# Flash_eMMC_MicroSD.net
KiCad netlist of a schematic drawn in Altium Designer
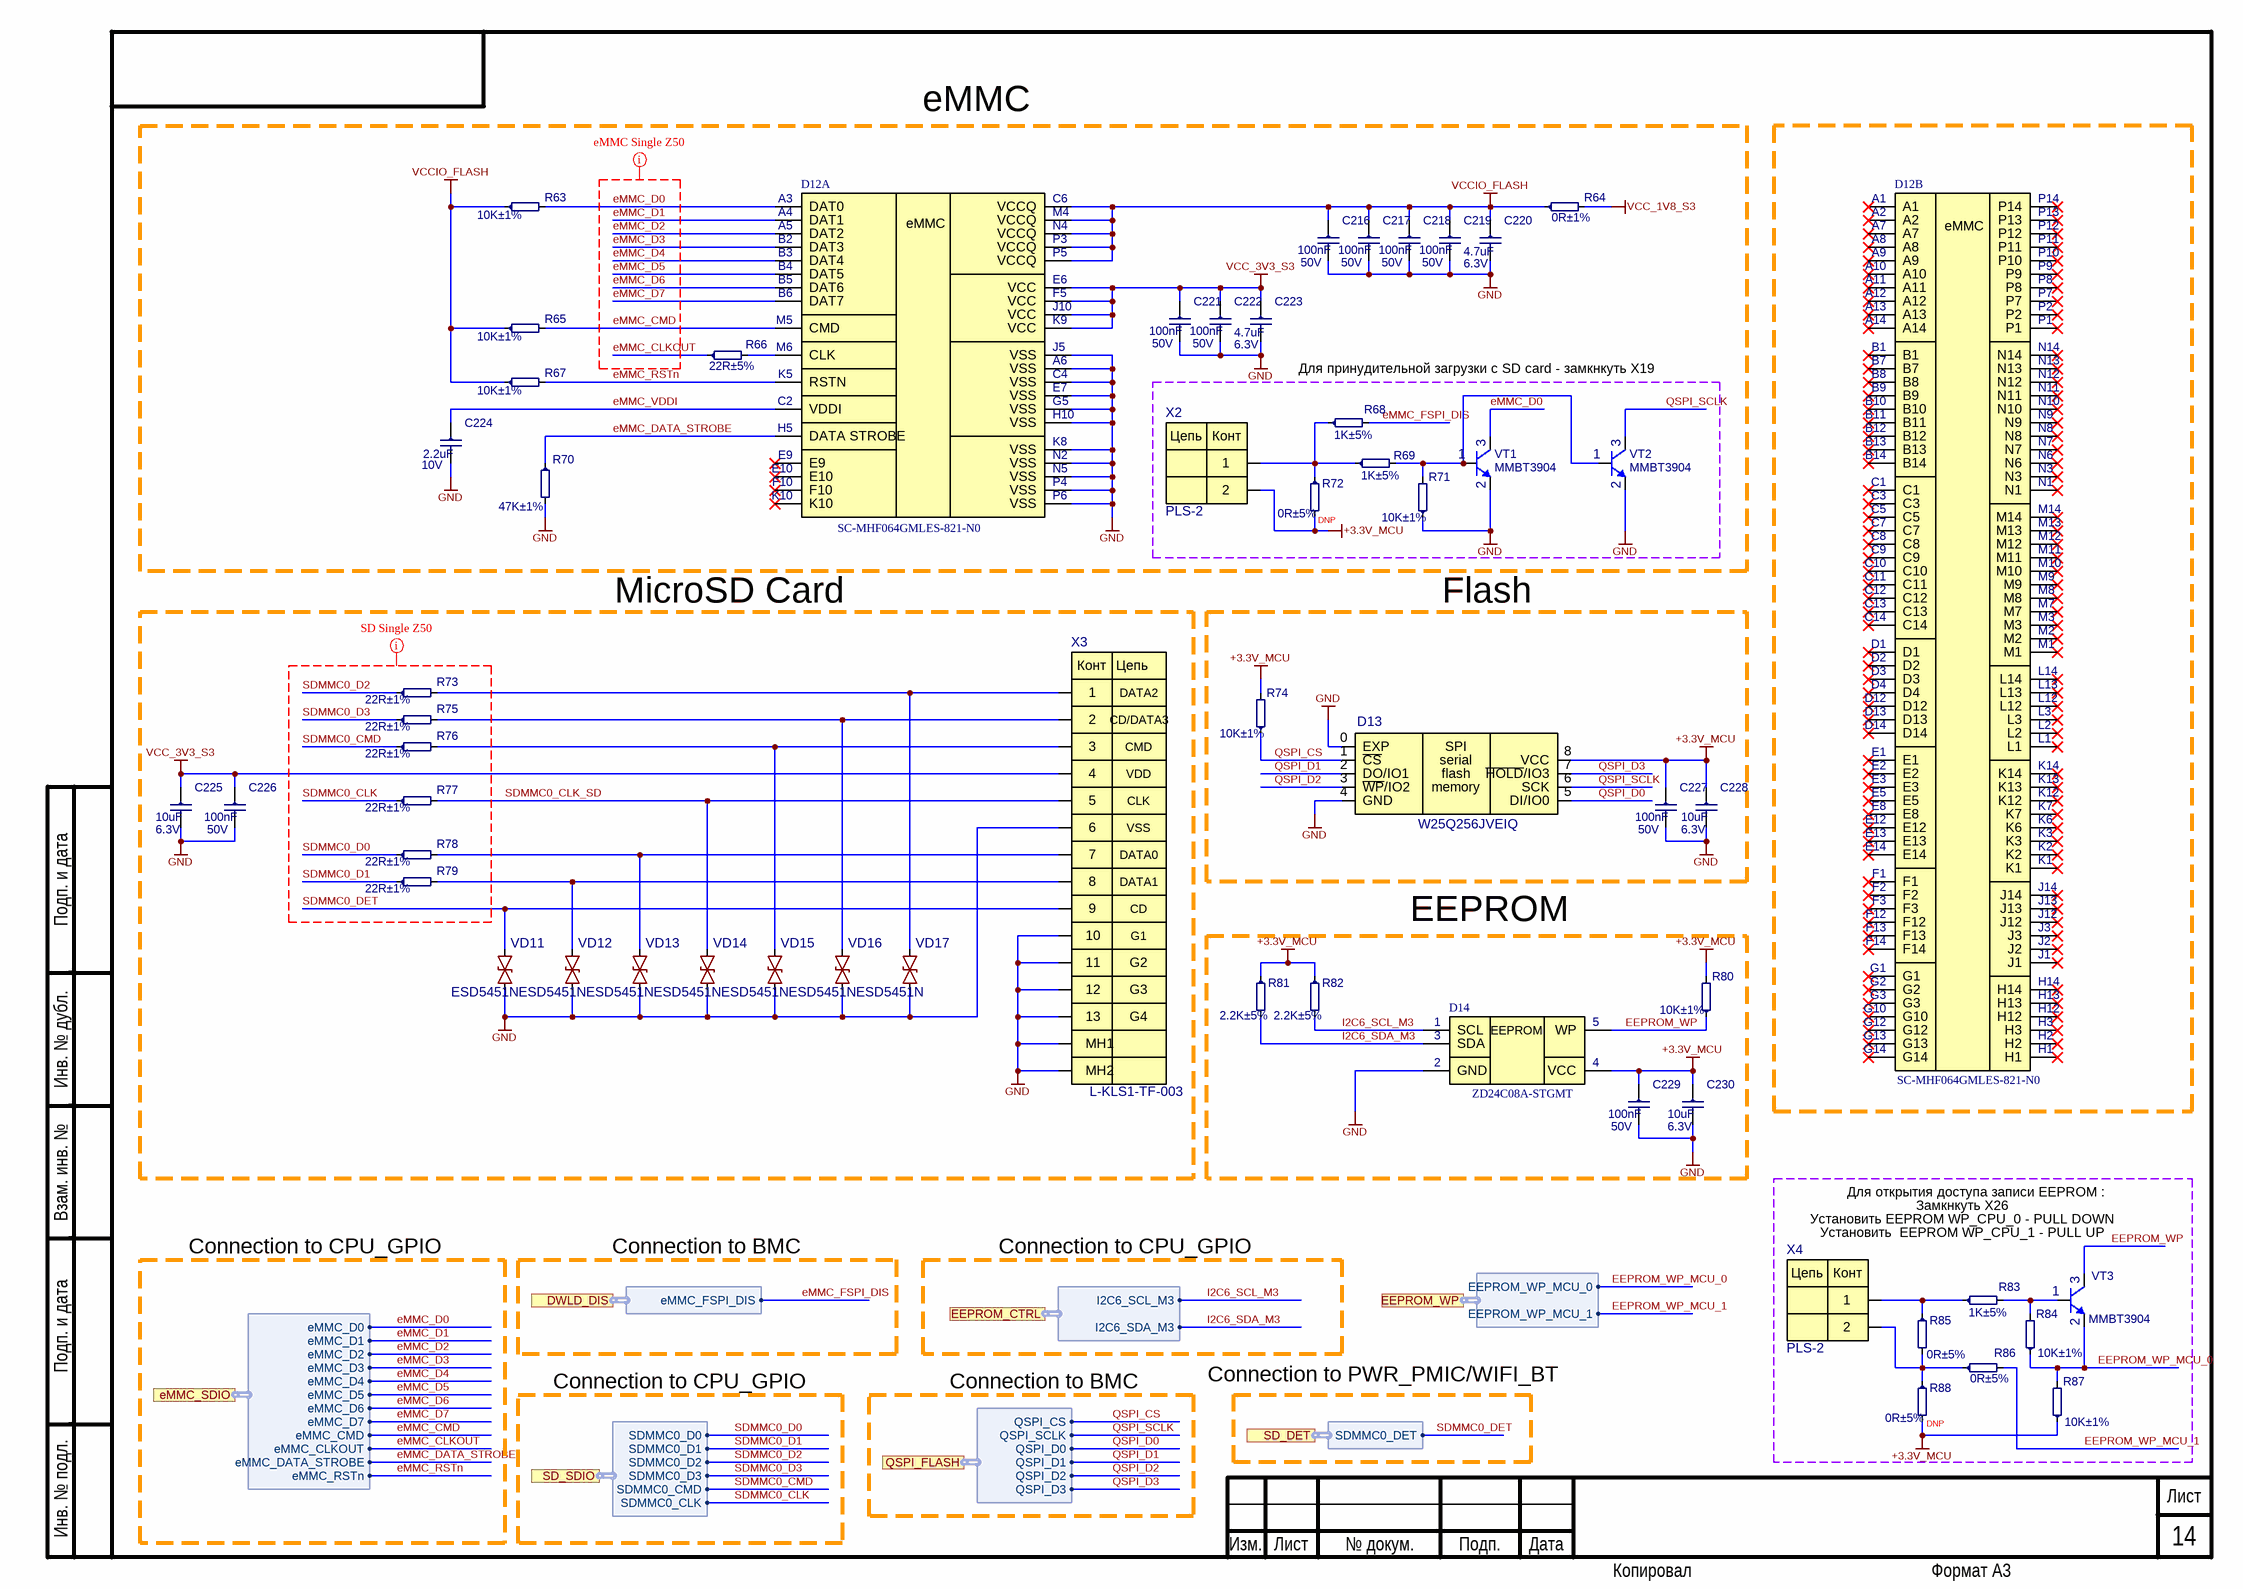
[diagram p0: Flash_eMMC_MicroSD.SchDoc]

(export (version "E")
  (design (tool "Eeschema 10.0.6"))
  (components
    (comp (ref "C216")
      (value "100nF")
      (footprint "C0402")
      (description "Ceramic Capacitor 0402 100nF ±10% 50V X7R")
      (fields
        (field (name "VOLTAGE") "50V")
        (field (name "PART NUMBER") "0402-X7R-50V-0.1uF±10%")
        (field (name "TOLERANCE") "10%")
      )
      (libsource (lib "ATB") (part "C"))
    )
    (comp (ref "C217")
      (value "100nF")
      (footprint "C0402")
      (description "Ceramic Capacitor 0402 100nF ±10% 50V X7R")
      (fields
        (field (name "VOLTAGE") "50V")
        (field (name "PART NUMBER") "0402-X7R-50V-0.1uF±10%")
        (field (name "TOLERANCE") "10%")
      )
      (libsource (lib "ATB") (part "C"))
    )
    (comp (ref "C218")
      (value "100nF")
      (footprint "C0402")
      (description "Ceramic Capacitor 0402 100nF ±10% 50V X7R")
      (fields
        (field (name "VOLTAGE") "50V")
        (field (name "PART NUMBER") "0402-X7R-50V-0.1uF±10%")
        (field (name "TOLERANCE") "10%")
      )
      (libsource (lib "ATB") (part "C"))
    )
    (comp (ref "C219")
      (value "100nF")
      (footprint "C0402")
      (description "Ceramic Capacitor 0402 100nF ±10% 50V X7R")
      (fields
        (field (name "VOLTAGE") "50V")
        (field (name "PART NUMBER") "0402-X7R-50V-0.1uF±10%")
        (field (name "TOLERANCE") "10%")
      )
      (libsource (lib "ATB") (part "C"))
    )
    (comp (ref "C220")
      (value "4.7uF")
      (footprint "C0402")
      (description "Ceramic Capacitor 0402 4.7uF ±20% 6.3V X5R")
      (fields
        (field (name "VOLTAGE") "6.3V")
        (field (name "PART NUMBER") "0402-X5R-6.3V-4.7uF±20%")
        (field (name "TOLERANCE") "20%")
      )
      (libsource (lib "ATB") (part "C"))
    )
    (comp (ref "C221")
      (value "100nF")
      (footprint "C0402")
      (description "Ceramic Capacitor 0402 100nF ±10% 50V X7R")
      (fields
        (field (name "VOLTAGE") "50V")
        (field (name "PART NUMBER") "0402-X7R-50V-0.1uF±10%")
        (field (name "TOLERANCE") "10%")
      )
      (libsource (lib "ATB") (part "C"))
    )
    (comp (ref "C222")
      (value "100nF")
      (footprint "C0402")
      (description "Ceramic Capacitor 0402 100nF ±10% 50V X7R")
      (fields
        (field (name "VOLTAGE") "50V")
        (field (name "PART NUMBER") "0402-X7R-50V-0.1uF±10%")
        (field (name "TOLERANCE") "10%")
      )
      (libsource (lib "ATB") (part "C"))
    )
    (comp (ref "C223")
      (value "4.7uF")
      (footprint "C0402")
      (description "Ceramic Capacitor 0402 4.7uF ±20% 6.3V X5R")
      (fields
        (field (name "VOLTAGE") "6.3V")
        (field (name "PART NUMBER") "0402-X5R-6.3V-4.7uF±20%")
        (field (name "TOLERANCE") "20%")
      )
      (libsource (lib "ATB") (part "C"))
    )
    (comp (ref "C224")
      (value "2.2uF")
      (footprint "C0402")
      (fields
        (field (name "VOLTAGE") "10V")
        (field (name "PART NUMBER") "0402-X5R-10V-2.2uF±10%")
        (field (name "TOLERANCE") "10%")
        (field (name "MANUFACTURER") "Yageo")
      )
      (libsource (lib "ATB") (part "C"))
    )
    (comp (ref "C225")
      (value "10uF")
      (footprint "C0402")
      (fields
        (field (name "VOLTAGE") "6.3V")
        (field (name "PART NUMBER") "0402-X5R-6.3V-10uF±20%")
        (field (name "TOLERANCE") "20%")
        (field (name "MANUFACTURER") "Yageo")
      )
      (libsource (lib "ATB") (part "C"))
    )
    (comp (ref "C226")
      (value "100nF")
      (footprint "C0402")
      (description "Ceramic Capacitor 0402 100nF ±10% 50V X7R")
      (fields
        (field (name "VOLTAGE") "50V")
        (field (name "PART NUMBER") "0402-X7R-50V-0.1uF±10%")
        (field (name "TOLERANCE") "10%")
      )
      (libsource (lib "ATB") (part "C"))
    )
    (comp (ref "C227")
      (value "100nF")
      (footprint "C0402")
      (description "Ceramic Capacitor 0402 100nF ±10% 50V X7R")
      (fields
        (field (name "VOLTAGE") "50V")
        (field (name "PART NUMBER") "0402-X7R-50V-0.1uF±10%")
        (field (name "TOLERANCE") "10%")
      )
      (libsource (lib "ATB") (part "C"))
    )
    (comp (ref "C228")
      (value "10uF")
      (footprint "C0402")
      (fields
        (field (name "VOLTAGE") "6.3V")
        (field (name "PART NUMBER") "0402-X5R-6.3V-10uF±20%")
        (field (name "TOLERANCE") "20%")
        (field (name "MANUFACTURER") "Yageo")
      )
      (libsource (lib "ATB") (part "C"))
    )
    (comp (ref "C229")
      (value "100nF")
      (footprint "C0402")
      (description "Ceramic Capacitor 0402 100nF ±10% 50V X7R")
      (fields
        (field (name "VOLTAGE") "50V")
        (field (name "PART NUMBER") "0402-X7R-50V-0.1uF±10%")
        (field (name "TOLERANCE") "10%")
      )
      (libsource (lib "ATB") (part "C"))
    )
    (comp (ref "C230")
      (value "10uF")
      (footprint "C0402")
      (fields
        (field (name "VOLTAGE") "6.3V")
        (field (name "PART NUMBER") "0402-X5R-6.3V-10uF±20%")
        (field (name "TOLERANCE") "20%")
        (field (name "MANUFACTURER") "Yageo")
      )
      (libsource (lib "ATB") (part "C"))
    )
    (comp (ref "D12")
      (value "SC-MHF064GMLES-821-N0")
      (footprint "SC-MHF064GMLES-821-N0")
      (description "Flash Card 64G-bytes 1.8V/3.3V Embedded MMC 153-Pin FBGA")
      (fields (field (name "MANUFACTURER") "Samsung"))
      (libsource (lib "LIB_RK") (part "SC-MHF064GMLES-821-N0"))
    )
    (comp (ref "D13")
      (value "W25Q256JVEIQ")
      (footprint "WSON-8-8x6")
      (description "3V 256M-BIT SERIAL FLASH MEMORY WITH DUAL/QUAD SPI")
      (fields (field (name "MANUFACTURER") "Winbond"))
      (libsource (lib "ATB") (part "W25Q64JVXGIQ"))
    )
    (comp (ref "D14")
      (value "ZD24C08A-STGMT")
      (footprint "ZD24C08A-STGMT")
      (description "8Kbit 1MHz I2C SOT-23-5 EEPROM")
      (fields (field (name "MANUFACTURER") "Zetta"))
      (libsource (lib "LIB_RK") (part "ZD24C08A-STGMT"))
    )
    (comp (ref "R63")
      (value "10K±1%")
      (footprint "R0402")
      (description "Chip Resistor 0402 10kΩ ±1% 50V ±100ppm/℃ Thick Film")
      (fields (field (name "PART NUMBER") "0402-0.0625W-10K-100ppm±1%") (field (name "TOLERANCE") "1%"))
      (libsource (lib "ATB") (part "R"))
    )
    (comp (ref "R64")
      (value "0R±1%")
      (footprint "R0603")
      (fields
        (field (name "PART NUMBER") "0603-0.1W-0R-200ppm±1%")
        (field (name "TOLERANCE") "1%")
        (field (name "MANUFACTURER") "Yageo")
      )
      (libsource (lib "ATB") (part "R"))
    )
    (comp (ref "R65")
      (value "10K±1%")
      (footprint "R0402")
      (description "Chip Resistor 0402 10kΩ ±1% 50V ±100ppm/℃ Thick Film")
      (fields (field (name "PART NUMBER") "0402-0.0625W-10K-100ppm±1%") (field (name "TOLERANCE") "1%"))
      (libsource (lib "ATB") (part "R"))
    )
    (comp (ref "R66")
      (value "22R±5%")
      (footprint "R0402")
      (fields
        (field (name "PART NUMBER") "0402-0.0625W-22R-100ppm±5%")
        (field (name "TOLERANCE") "5%")
        (field (name "MANUFACTURER") "Yageo")
      )
      (libsource (lib "ATB") (part "R"))
    )
    (comp (ref "R67")
      (value "10K±1%")
      (footprint "R0402")
      (description "Chip Resistor 0402 10kΩ ±1% 50V ±100ppm/℃ Thick Film")
      (fields (field (name "PART NUMBER") "0402-0.0625W-10K-100ppm±1%") (field (name "TOLERANCE") "1%"))
      (libsource (lib "ATB") (part "R"))
    )
    (comp (ref "R68")
      (value "1K±5%")
      (footprint "R0402")
      (fields
        (field (name "PART NUMBER") "0402-0.0625W-1K-100ppm±5%")
        (field (name "TOLERANCE") "5%")
        (field (name "MANUFACTURER") "Yageo")
      )
      (libsource (lib "ATB") (part "R"))
    )
    (comp (ref "R69")
      (value "1K±5%")
      (footprint "R0402")
      (fields
        (field (name "PART NUMBER") "0402-0.0625W-1K-100ppm±5%")
        (field (name "TOLERANCE") "5%")
        (field (name "MANUFACTURER") "Yageo")
      )
      (libsource (lib "ATB") (part "R"))
    )
    (comp (ref "R70")
      (value "47K±1%")
      (footprint "R0402")
      (fields
        (field (name "PART NUMBER") "0402-0.0625W-47K-100ppm±1%")
        (field (name "TOLERANCE") "1%")
        (field (name "MANUFACTURER") "Yageo")
      )
      (libsource (lib "ATB") (part "R"))
    )
    (comp (ref "R71")
      (value "10K±1%")
      (footprint "R0402")
      (description "Chip Resistor 0402 10kΩ ±1% 50V ±100ppm/℃ Thick Film")
      (fields (field (name "PART NUMBER") "0402-0.0625W-10K-100ppm±1%") (field (name "TOLERANCE") "1%"))
      (libsource (lib "ATB") (part "R"))
    )
    (comp (ref "R72")
      (value "0R±5%")
      (footprint "R0402")
      (fields
        (field (name "PART NUMBER") "0402-0.0625W-0R-100ppm±5%")
        (field (name "TOLERANCE") "5%")
        (field (name "MANUFACTURER") "Yageo")
      )
      (libsource (lib "ATB") (part "R"))
    )
    (comp (ref "R73")
      (value "22R±1%")
      (footprint "R0402")
      (description "Chip Resistor 0402 22Ω ±1% 50V ±100ppm/℃ Thick Film")
      (fields (field (name "PART NUMBER") "0402-0.0625W-22R-100ppm±1%") (field (name "TOLERANCE") "1%"))
      (libsource (lib "ATB") (part "R"))
    )
    (comp (ref "R74")
      (value "10K±1%")
      (footprint "R0402")
      (description "Chip Resistor 0402 10kΩ ±1% 50V ±100ppm/℃ Thick Film")
      (fields (field (name "PART NUMBER") "0402-0.0625W-10K-100ppm±1%") (field (name "TOLERANCE") "1%"))
      (libsource (lib "ATB") (part "R"))
    )
    (comp (ref "R75")
      (value "22R±1%")
      (footprint "R0402")
      (description "Chip Resistor 0402 22Ω ±1% 50V ±100ppm/℃ Thick Film")
      (fields (field (name "PART NUMBER") "0402-0.0625W-22R-100ppm±1%") (field (name "TOLERANCE") "1%"))
      (libsource (lib "ATB") (part "R"))
    )
    (comp (ref "R76")
      (value "22R±1%")
      (footprint "R0402")
      (description "Chip Resistor 0402 22Ω ±1% 50V ±100ppm/℃ Thick Film")
      (fields (field (name "PART NUMBER") "0402-0.0625W-22R-100ppm±1%") (field (name "TOLERANCE") "1%"))
      (libsource (lib "ATB") (part "R"))
    )
    (comp (ref "R77")
      (value "22R±1%")
      (footprint "R0402")
      (description "Chip Resistor 0402 22Ω ±1% 50V ±100ppm/℃ Thick Film")
      (fields (field (name "PART NUMBER") "0402-0.0625W-22R-100ppm±1%") (field (name "TOLERANCE") "1%"))
      (libsource (lib "ATB") (part "R"))
    )
    (comp (ref "R78")
      (value "22R±1%")
      (footprint "R0402")
      (description "Chip Resistor 0402 22Ω ±1% 50V ±100ppm/℃ Thick Film")
      (fields (field (name "PART NUMBER") "0402-0.0625W-22R-100ppm±1%") (field (name "TOLERANCE") "1%"))
      (libsource (lib "ATB") (part "R"))
    )
    (comp (ref "R79")
      (value "22R±1%")
      (footprint "R0402")
      (description "Chip Resistor 0402 22Ω ±1% 50V ±100ppm/℃ Thick Film")
      (fields (field (name "PART NUMBER") "0402-0.0625W-22R-100ppm±1%") (field (name "TOLERANCE") "1%"))
      (libsource (lib "ATB") (part "R"))
    )
    (comp (ref "R80")
      (value "10K±1%")
      (footprint "R0402")
      (description "Chip Resistor 0402 10kΩ ±1% 50V ±100ppm/℃ Thick Film")
      (fields (field (name "PART NUMBER") "0402-0.0625W-10K-100ppm±1%") (field (name "TOLERANCE") "1%"))
      (libsource (lib "ATB") (part "R"))
    )
    (comp (ref "R81")
      (value "2.2K±5%")
      (footprint "R0402")
      (fields
        (field (name "PART NUMBER") "0402-0.0625W-2.2K-100ppm±5%")
        (field (name "TOLERANCE") "5%")
        (field (name "MANUFACTURER") "Yageo")
      )
      (libsource (lib "ATB") (part "R"))
    )
    (comp (ref "R82")
      (value "2.2K±5%")
      (footprint "R0402")
      (fields
        (field (name "PART NUMBER") "0402-0.0625W-2.2K-100ppm±5%")
        (field (name "TOLERANCE") "5%")
        (field (name "MANUFACTURER") "Yageo")
      )
      (libsource (lib "ATB") (part "R"))
    )
    (comp (ref "R83")
      (value "1K±5%")
      (footprint "R0402")
      (fields
        (field (name "PART NUMBER") "0402-0.0625W-1K-100ppm±5%")
        (field (name "TOLERANCE") "5%")
        (field (name "MANUFACTURER") "Yageo")
      )
      (libsource (lib "ATB") (part "R"))
    )
    (comp (ref "R84")
      (value "10K±1%")
      (footprint "R0402")
      (description "Chip Resistor 0402 10kΩ ±1% 50V ±100ppm/℃ Thick Film")
      (fields (field (name "PART NUMBER") "0402-0.0625W-10K-100ppm±1%") (field (name "TOLERANCE") "1%"))
      (libsource (lib "ATB") (part "R"))
    )
    (comp (ref "R85")
      (value "0R±5%")
      (footprint "R0402")
      (fields
        (field (name "PART NUMBER") "0402-0.0625W-0R-100ppm±5%")
        (field (name "TOLERANCE") "5%")
        (field (name "MANUFACTURER") "Yageo")
      )
      (libsource (lib "ATB") (part "R"))
    )
    (comp (ref "R86")
      (value "0R±5%")
      (footprint "R0402")
      (fields
        (field (name "PART NUMBER") "0402-0.0625W-0R-100ppm±5%")
        (field (name "TOLERANCE") "5%")
        (field (name "MANUFACTURER") "Yageo")
      )
      (libsource (lib "ATB") (part "R"))
    )
    (comp (ref "R87")
      (value "10K±1%")
      (footprint "R0402")
      (description "Chip Resistor 0402 10kΩ ±1% 50V ±100ppm/℃ Thick Film")
      (fields (field (name "PART NUMBER") "0402-0.0625W-10K-100ppm±1%") (field (name "TOLERANCE") "1%"))
      (libsource (lib "ATB") (part "R"))
    )
    (comp (ref "R88")
      (value "0R±5%")
      (footprint "R0402")
      (fields
        (field (name "PART NUMBER") "0402-0.0625W-0R-100ppm±5%")
        (field (name "TOLERANCE") "5%")
        (field (name "MANUFACTURER") "Yageo")
      )
      (libsource (lib "ATB") (part "R"))
    )
    (comp (ref "VD11")
      (value "ESD5451N")
      (footprint "DFN_1006_2")
      (description "Bidirectional TVS Diode 5V")
      (fields (field (name "MANUFACTURER") "Tech Public Co."))
      (libsource (lib "ATB") (part "ESD-BiDirectional"))
    )
    (comp (ref "VD12")
      (value "ESD5451N")
      (footprint "DFN_1006_2")
      (description "Bidirectional TVS Diode 5V")
      (fields (field (name "MANUFACTURER") "Tech Public Co."))
      (libsource (lib "ATB") (part "ESD-BiDirectional"))
    )
    (comp (ref "VD13")
      (value "ESD5451N")
      (footprint "DFN_1006_2")
      (description "Bidirectional TVS Diode 5V")
      (fields (field (name "MANUFACTURER") "Tech Public Co."))
      (libsource (lib "ATB") (part "ESD-BiDirectional"))
    )
    (comp (ref "VD14")
      (value "ESD5451N")
      (footprint "DFN_1006_2")
      (description "Bidirectional TVS Diode 5V")
      (fields (field (name "MANUFACTURER") "Tech Public Co."))
      (libsource (lib "ATB") (part "ESD-BiDirectional"))
    )
    (comp (ref "VD15")
      (value "ESD5451N")
      (footprint "DFN_1006_2")
      (description "Bidirectional TVS Diode 5V")
      (fields (field (name "MANUFACTURER") "Tech Public Co."))
      (libsource (lib "ATB") (part "ESD-BiDirectional"))
    )
    (comp (ref "VD16")
      (value "ESD5451N")
      (footprint "DFN_1006_2")
      (description "Bidirectional TVS Diode 5V")
      (fields (field (name "MANUFACTURER") "Tech Public Co."))
      (libsource (lib "ATB") (part "ESD-BiDirectional"))
    )
    (comp (ref "VD17")
      (value "ESD5451N")
      (footprint "DFN_1006_2")
      (description "Bidirectional TVS Diode 5V")
      (fields (field (name "MANUFACTURER") "Tech Public Co."))
      (libsource (lib "ATB") (part "ESD-BiDirectional"))
    )
    (comp (ref "VT1")
      (value "MMBT3904")
      (footprint "SOT23")
      (description "NPN transistor")
      (fields (field (name "VOLTAGE") "40V") (field (name "MANUFACTURER") "Diotec Semiconductor"))
      (libsource (lib "ATB") (part "BC846BLT1G"))
    )
    (comp (ref "VT2")
      (value "MMBT3904")
      (footprint "SOT23")
      (description "NPN transistor")
      (fields (field (name "VOLTAGE") "40V") (field (name "MANUFACTURER") "Diotec Semiconductor"))
      (libsource (lib "ATB") (part "BC846BLT1G"))
    )
    (comp (ref "VT3")
      (value "MMBT3904")
      (footprint "SOT23")
      (description "NPN transistor")
      (fields (field (name "VOLTAGE") "40V") (field (name "MANUFACTURER") "Diotec Semiconductor"))
      (libsource (lib "ATB") (part "BC846BLT1G"))
    )
    (comp (ref "X2")
      (value "PLS-2")
      (footprint "PLS2")
      (description "Terminal block 2")
      (fields (field (name "MANUFACTURER") "NXU"))
      (libsource (lib "ATB") (part "H2"))
    )
    (comp (ref "X3")
      (value "L-KLS1-TF-003")
      (footprint "KLS1-TF-003")
      (description "L-KLS1-TF-003 Push-Push H1.85mm With CD Pin Micro SD Card Connector")
      (fields (field (name "MANUFACTURER") "KLS"))
      (libsource (lib "LIB_RK") (part "KLS1-TF-003"))
    )
    (comp (ref "X4")
      (value "PLS-2")
      (footprint "PLS2")
      (description "Terminal block 2")
      (fields (field (name "MANUFACTURER") "NXU"))
      (libsource (lib "ATB") (part "H2"))
    )
  )
  (nets
    (net (code "7") (name "+3.3V_MCU") (class "Default")
      (node (ref "C227") (pin "1") (pinfunction "1_1") (pintype "passive"))
      (node (ref "C228") (pin "1") (pinfunction "1_1") (pintype "passive"))
      (node (ref "C229") (pin "1") (pinfunction "1_1") (pintype "passive"))
      (node (ref "C230") (pin "1") (pinfunction "1_1") (pintype "passive"))
      (node (ref "D13") (pin "8") (pinfunction "VCC_8") (pintype "passive"))
      (node (ref "D14") (pin "4") (pinfunction "VCC_4") (pintype "passive"))
      (node (ref "R72") (pin "2") (pinfunction "2_2") (pintype "passive"))
      (node (ref "R74") (pin "2") (pinfunction "2_2") (pintype "passive"))
      (node (ref "R80") (pin "2") (pinfunction "2_2") (pintype "passive"))
      (node (ref "R81") (pin "1") (pinfunction "1_1") (pintype "passive"))
      (node (ref "R82") (pin "1") (pinfunction "1_1") (pintype "passive"))
      (node (ref "R87") (pin "1") (pinfunction "1_1") (pintype "passive"))
      (node (ref "R88") (pin "2") (pinfunction "2_2") (pintype "passive"))
      (node (ref "X2") (pin "2") (pinfunction "2_2") (pintype "passive"))
    )
    (net (code "8") (name "/EEPROM_WP") (class "Default")
      (node (ref "D14") (pin "5") (pinfunction "WP_5") (pintype "passive"))
      (node (ref "R80") (pin "1") (pinfunction "1_1") (pintype "passive"))
      (node (ref "VT3") (pin "3") (pinfunction "C_3") (pintype "passive"))
    )
    (net (code "9") (name "/EEPROM_WP_MCU_0") (class "Default")
      (node (ref "R84") (pin "1") (pinfunction "1_1") (pintype "passive"))
      (node (ref "R87") (pin "2") (pinfunction "2_2") (pintype "passive"))
      (node (ref "VT3") (pin "2") (pinfunction "E_2") (pintype "passive"))
    )
    (net (code "10") (name "/EEPROM_WP_MCU_1") (class "Default")
      (node (ref "R86") (pin "2") (pinfunction "2_2") (pintype "passive"))
    )
    (net (code "11") (name "/I2C6_SCL_M3") (class "Default")
      (node (ref "D14") (pin "1") (pinfunction "SCL_1") (pintype "passive"))
      (node (ref "R82") (pin "2") (pinfunction "2_2") (pintype "passive"))
    )
    (net (code "12") (name "/I2C6_SDA_M3") (class "Default")
      (node (ref "D14") (pin "3") (pinfunction "SDA_3") (pintype "passive"))
      (node (ref "R81") (pin "2") (pinfunction "2_2") (pintype "passive"))
    )
    (net (code "13") (name "/QSPI_CS") (class "Default")
      (node (ref "D13") (pin "1") (pinfunction "~{CS}_1") (pintype "passive"))
      (node (ref "R74") (pin "1") (pinfunction "1_1") (pintype "passive"))
    )
    (net (code "14") (name "/QSPI_D0") (class "Default")
      (node (ref "D13") (pin "5") (pinfunction "DI/IO0_5") (pintype "passive"))
    )
    (net (code "15") (name "/QSPI_D1") (class "Default")
      (node (ref "D13") (pin "2") (pinfunction "DO/IO1_2") (pintype "passive"))
    )
    (net (code "16") (name "/QSPI_D2") (class "Default")
      (node (ref "D13") (pin "3") (pinfunction "~{WP}/IO2_3") (pintype "passive"))
    )
    (net (code "17") (name "/QSPI_D3") (class "Default")
      (node (ref "D13") (pin "7") (pinfunction "~{HOLD}/IO3_7") (pintype "passive"))
    )
    (net (code "18") (name "/QSPI_SCLK") (class "Default")
      (node (ref "D13") (pin "6") (pinfunction "SCK_6") (pintype "passive"))
      (node (ref "VT2") (pin "3") (pinfunction "C_3") (pintype "passive"))
    )
    (net (code "19") (name "/SDMMC0_CLK") (class "Default")
      (node (ref "R77") (pin "1") (pinfunction "1_1") (pintype "passive"))
    )
    (net (code "20") (name "/SDMMC0_CLK_SD") (class "Default")
      (node (ref "R77") (pin "2") (pinfunction "2_2") (pintype "passive"))
      (node (ref "VD14") (pin "1") (pinfunction "1_1") (pintype "passive"))
      (node (ref "X3") (pin "5") (pinfunction "5_5") (pintype "passive"))
    )
    (net (code "21") (name "/SDMMC0_CMD") (class "Default")
      (node (ref "R76") (pin "1") (pinfunction "1_1") (pintype "passive"))
    )
    (net (code "22") (name "/SDMMC0_D0") (class "Default")
      (node (ref "R78") (pin "1") (pinfunction "1_1") (pintype "passive"))
    )
    (net (code "23") (name "/SDMMC0_D1") (class "Default")
      (node (ref "R79") (pin "1") (pinfunction "1_1") (pintype "passive"))
    )
    (net (code "24") (name "/SDMMC0_D2") (class "Default")
      (node (ref "R73") (pin "1") (pinfunction "1_1") (pintype "passive"))
    )
    (net (code "25") (name "/SDMMC0_D3") (class "Default")
      (node (ref "R75") (pin "1") (pinfunction "1_1") (pintype "passive"))
    )
    (net (code "26") (name "/SDMMC0_DET") (class "Default")
      (node (ref "VD11") (pin "1") (pinfunction "1_1") (pintype "passive"))
      (node (ref "X3") (pin "9") (pinfunction "9_9") (pintype "passive"))
    )
    (net (code "27") (name "/eMMC_CLKOUT") (class "Default")
      (node (ref "R66") (pin "1") (pinfunction "1_1") (pintype "passive"))
    )
    (net (code "28") (name "/eMMC_CMD") (class "Default")
      (node (ref "D12") (pin "M5") (pinfunction "CMD_M5") (pintype "passive"))
      (node (ref "R65") (pin "2") (pinfunction "2_2") (pintype "passive"))
    )
    (net (code "29") (name "/eMMC_D0") (class "Default")
      (node (ref "D12") (pin "A3") (pinfunction "DAT0_A3") (pintype "passive"))
      (node (ref "R63") (pin "2") (pinfunction "2_2") (pintype "passive"))
      (node (ref "VT1") (pin "3") (pinfunction "C_3") (pintype "passive"))
    )
    (net (code "30") (name "/eMMC_D1") (class "Default")
      (node (ref "D12") (pin "A4") (pinfunction "DAT1_A4") (pintype "passive"))
    )
    (net (code "31") (name "/eMMC_D2") (class "Default")
      (node (ref "D12") (pin "A5") (pinfunction "DAT2_A5") (pintype "passive"))
    )
    (net (code "32") (name "/eMMC_D3") (class "Default")
      (node (ref "D12") (pin "B2") (pinfunction "DAT3_B2") (pintype "passive"))
    )
    (net (code "33") (name "/eMMC_D4") (class "Default")
      (node (ref "D12") (pin "B3") (pinfunction "DAT4_B3") (pintype "passive"))
    )
    (net (code "34") (name "/eMMC_D5") (class "Default")
      (node (ref "D12") (pin "B4") (pinfunction "DAT5_B4") (pintype "passive"))
    )
    (net (code "35") (name "/eMMC_D6") (class "Default")
      (node (ref "D12") (pin "B5") (pinfunction "DAT6_B5") (pintype "passive"))
    )
    (net (code "36") (name "/eMMC_D7") (class "Default")
      (node (ref "D12") (pin "B6") (pinfunction "DAT7_B6") (pintype "passive"))
    )
    (net (code "37") (name "/eMMC_DATA_STROBE") (class "Default")
      (node (ref "D12") (pin "H5") (pinfunction "DATA_STROBE_H5") (pintype "passive"))
      (node (ref "R70") (pin "1") (pinfunction "1_1") (pintype "passive"))
    )
    (net (code "38") (name "/eMMC_FSPI_DIS") (class "Default")
      (node (ref "R68") (pin "2") (pinfunction "2_2") (pintype "passive"))
    )
    (net (code "39") (name "/eMMC_RSTn") (class "Default")
      (node (ref "D12") (pin "K5") (pinfunction "RSTN_K5") (pintype "passive"))
      (node (ref "R67") (pin "2") (pinfunction "2_2") (pintype "passive"))
    )
    (net (code "40") (name "/eMMC_VDDI") (class "Default")
      (node (ref "C224") (pin "1") (pinfunction "1_1") (pintype "passive"))
      (node (ref "D12") (pin "C2") (pinfunction "VDDI_C2") (pintype "passive"))
    )
    (net (code "48") (name "GND") (class "Default")
      (node (ref "C216") (pin "2") (pinfunction "2_2") (pintype "passive"))
      (node (ref "C217") (pin "2") (pinfunction "2_2") (pintype "passive"))
      (node (ref "C218") (pin "2") (pinfunction "2_2") (pintype "passive"))
      (node (ref "C219") (pin "2") (pinfunction "2_2") (pintype "passive"))
      (node (ref "C220") (pin "2") (pinfunction "2_2") (pintype "passive"))
      (node (ref "C221") (pin "2") (pinfunction "2_2") (pintype "passive"))
      (node (ref "C222") (pin "2") (pinfunction "2_2") (pintype "passive"))
      (node (ref "C223") (pin "2") (pinfunction "2_2") (pintype "passive"))
      (node (ref "C224") (pin "2") (pinfunction "2_2") (pintype "passive"))
      (node (ref "C225") (pin "2") (pinfunction "2_2") (pintype "passive"))
      (node (ref "C226") (pin "2") (pinfunction "2_2") (pintype "passive"))
      (node (ref "C227") (pin "2") (pinfunction "2_2") (pintype "passive"))
      (node (ref "C228") (pin "2") (pinfunction "2_2") (pintype "passive"))
      (node (ref "C229") (pin "2") (pinfunction "2_2") (pintype "passive"))
      (node (ref "C230") (pin "2") (pinfunction "2_2") (pintype "passive"))
      (node (ref "D12") (pin "A6") (pinfunction "VSS_A6") (pintype "passive"))
      (node (ref "D12") (pin "C4") (pinfunction "VSS_C4") (pintype "passive"))
      (node (ref "D12") (pin "E7") (pinfunction "VSS_E7") (pintype "passive"))
      (node (ref "D12") (pin "G5") (pinfunction "VSS_G5") (pintype "passive"))
      (node (ref "D12") (pin "H10") (pinfunction "VSS_H10") (pintype "passive"))
      (node (ref "D12") (pin "J5") (pinfunction "VSS_J5") (pintype "passive"))
      (node (ref "D12") (pin "K8") (pinfunction "VSS_K8") (pintype "passive"))
      (node (ref "D12") (pin "N2") (pinfunction "VSS_N2") (pintype "passive"))
      (node (ref "D12") (pin "N5") (pinfunction "VSS_N5") (pintype "passive"))
      (node (ref "D12") (pin "P4") (pinfunction "VSS_P4") (pintype "passive"))
      (node (ref "D12") (pin "P6") (pinfunction "VSS_P6") (pintype "passive"))
      (node (ref "D13") (pin "0") (pinfunction "EXP_0") (pintype "passive"))
      (node (ref "D13") (pin "4") (pinfunction "GND_4") (pintype "passive"))
      (node (ref "D14") (pin "2") (pinfunction "GND_2") (pintype "passive"))
      (node (ref "R70") (pin "2") (pinfunction "2_2") (pintype "passive"))
      (node (ref "R71") (pin "1") (pinfunction "1_1") (pintype "passive"))
      (node (ref "VD11") (pin "2") (pinfunction "2_2") (pintype "passive"))
      (node (ref "VD12") (pin "2") (pinfunction "2_2") (pintype "passive"))
      (node (ref "VD13") (pin "2") (pinfunction "2_2") (pintype "passive"))
      (node (ref "VD14") (pin "2") (pinfunction "2_2") (pintype "passive"))
      (node (ref "VD15") (pin "2") (pinfunction "2_2") (pintype "passive"))
      (node (ref "VD16") (pin "2") (pinfunction "2_2") (pintype "passive"))
      (node (ref "VD17") (pin "2") (pinfunction "2_2") (pintype "passive"))
      (node (ref "VT1") (pin "2") (pinfunction "E_2") (pintype "passive"))
      (node (ref "VT2") (pin "2") (pinfunction "E_2") (pintype "passive"))
      (node (ref "X3") (pin "10") (pinfunction "10_10") (pintype "passive"))
      (node (ref "X3") (pin "11") (pinfunction "11_11") (pintype "passive"))
      (node (ref "X3") (pin "12") (pinfunction "12_12") (pintype "passive"))
      (node (ref "X3") (pin "13") (pinfunction "13_13") (pintype "passive"))
      (node (ref "X3") (pin "6") (pinfunction "6_6") (pintype "passive"))
      (node (ref "X3") (pin "MH1") (pinfunction "MH1_MH1") (pintype "passive"))
      (node (ref "X3") (pin "MH2") (pinfunction "MH2_MH2") (pintype "passive"))
    )
    (net (code "49") (name "Net-(D12A-CLK)") (class "Default")
      (node (ref "D12") (pin "M6") (pinfunction "CLK_M6") (pintype "passive"))
      (node (ref "R66") (pin "2") (pinfunction "2_2") (pintype "passive"))
    )
    (net (code "50") (name "Net-(R68-Pad1)") (class "Default")
      (node (ref "R68") (pin "1") (pinfunction "1_1") (pintype "passive"))
      (node (ref "R69") (pin "1") (pinfunction "1_1") (pintype "passive"))
      (node (ref "R72") (pin "1") (pinfunction "1_1") (pintype "passive"))
      (node (ref "X2") (pin "1") (pinfunction "1_1") (pintype "passive"))
    )
    (net (code "51") (name "Net-(R73-Pad2)") (class "Default")
      (node (ref "R73") (pin "2") (pinfunction "2_2") (pintype "passive"))
      (node (ref "VD17") (pin "1") (pinfunction "1_1") (pintype "passive"))
      (node (ref "X3") (pin "1") (pinfunction "1_1") (pintype "passive"))
    )
    (net (code "52") (name "Net-(R75-Pad2)") (class "Default")
      (node (ref "R75") (pin "2") (pinfunction "2_2") (pintype "passive"))
      (node (ref "VD16") (pin "1") (pinfunction "1_1") (pintype "passive"))
      (node (ref "X3") (pin "2") (pinfunction "2_2") (pintype "passive"))
    )
    (net (code "53") (name "Net-(R76-Pad2)") (class "Default")
      (node (ref "R76") (pin "2") (pinfunction "2_2") (pintype "passive"))
      (node (ref "VD15") (pin "1") (pinfunction "1_1") (pintype "passive"))
      (node (ref "X3") (pin "3") (pinfunction "3_3") (pintype "passive"))
    )
    (net (code "54") (name "Net-(R78-Pad2)") (class "Default")
      (node (ref "R78") (pin "2") (pinfunction "2_2") (pintype "passive"))
      (node (ref "VD13") (pin "1") (pinfunction "1_1") (pintype "passive"))
      (node (ref "X3") (pin "7") (pinfunction "7_7") (pintype "passive"))
    )
    (net (code "55") (name "Net-(R79-Pad2)") (class "Default")
      (node (ref "R79") (pin "2") (pinfunction "2_2") (pintype "passive"))
      (node (ref "VD12") (pin "1") (pinfunction "1_1") (pintype "passive"))
      (node (ref "X3") (pin "8") (pinfunction "8_8") (pintype "passive"))
    )
    (net (code "56") (name "Net-(R83-Pad1)") (class "Default")
      (node (ref "R83") (pin "1") (pinfunction "1_1") (pintype "passive"))
      (node (ref "R85") (pin "1") (pinfunction "1_1") (pintype "passive"))
      (node (ref "X4") (pin "1") (pinfunction "1_1") (pintype "passive"))
    )
    (net (code "57") (name "Net-(R85-Pad2)") (class "Default")
      (node (ref "R85") (pin "2") (pinfunction "2_2") (pintype "passive"))
      (node (ref "R86") (pin "1") (pinfunction "1_1") (pintype "passive"))
      (node (ref "R88") (pin "1") (pinfunction "1_1") (pintype "passive"))
      (node (ref "X4") (pin "2") (pinfunction "2_2") (pintype "passive"))
    )
    (net (code "58") (name "Net-(VT1-B)") (class "Default")
      (node (ref "R69") (pin "2") (pinfunction "2_2") (pintype "passive"))
      (node (ref "R71") (pin "2") (pinfunction "2_2") (pintype "passive"))
      (node (ref "VT1") (pin "1") (pinfunction "B_1") (pintype "passive"))
      (node (ref "VT2") (pin "1") (pinfunction "B_1") (pintype "passive"))
    )
    (net (code "59") (name "Net-(VT3-B)") (class "Default")
      (node (ref "R83") (pin "2") (pinfunction "2_2") (pintype "passive"))
      (node (ref "R84") (pin "2") (pinfunction "2_2") (pintype "passive"))
      (node (ref "VT3") (pin "1") (pinfunction "B_1") (pintype "passive"))
    )
    (net (code "60") (name "VCCIO_FLASH") (class "Default")
      (node (ref "C216") (pin "1") (pinfunction "1_1") (pintype "passive"))
      (node (ref "C217") (pin "1") (pinfunction "1_1") (pintype "passive"))
      (node (ref "C218") (pin "1") (pinfunction "1_1") (pintype "passive"))
      (node (ref "C219") (pin "1") (pinfunction "1_1") (pintype "passive"))
      (node (ref "C220") (pin "1") (pinfunction "1_1") (pintype "passive"))
      (node (ref "D12") (pin "C6") (pinfunction "VCCQ_C6") (pintype "passive"))
      (node (ref "D12") (pin "M4") (pinfunction "VCCQ_M4") (pintype "passive"))
      (node (ref "D12") (pin "N4") (pinfunction "VCCQ_N4") (pintype "passive"))
      (node (ref "D12") (pin "P3") (pinfunction "VCCQ_P3") (pintype "passive"))
      (node (ref "D12") (pin "P5") (pinfunction "VCCQ_P5") (pintype "passive"))
      (node (ref "R63") (pin "1") (pinfunction "1_1") (pintype "passive"))
      (node (ref "R64") (pin "1") (pinfunction "1_1") (pintype "passive"))
      (node (ref "R65") (pin "1") (pinfunction "1_1") (pintype "passive"))
      (node (ref "R67") (pin "1") (pinfunction "1_1") (pintype "passive"))
    )
    (net (code "61") (name "VCC_1V8_S3") (class "Default")
      (node (ref "R64") (pin "2") (pinfunction "2_2") (pintype "passive"))
    )
    (net (code "62") (name "VCC_3V3_S3") (class "Default")
      (node (ref "C221") (pin "1") (pinfunction "1_1") (pintype "passive"))
      (node (ref "C222") (pin "1") (pinfunction "1_1") (pintype "passive"))
      (node (ref "C223") (pin "1") (pinfunction "1_1") (pintype "passive"))
      (node (ref "C225") (pin "1") (pinfunction "1_1") (pintype "passive"))
      (node (ref "C226") (pin "1") (pinfunction "1_1") (pintype "passive"))
      (node (ref "D12") (pin "E6") (pinfunction "VCC_E6") (pintype "passive"))
      (node (ref "D12") (pin "F5") (pinfunction "VCC_F5") (pintype "passive"))
      (node (ref "D12") (pin "J10") (pinfunction "VCC_J10") (pintype "passive"))
      (node (ref "D12") (pin "K9") (pinfunction "VCC_K9") (pintype "passive"))
      (node (ref "X3") (pin "4") (pinfunction "4_4") (pintype "passive"))
    )
    (net (code "63") (name "unconnected-(D12-PadA1)") (class "Default")
      (node (ref "D12") (pin "A1") (pinfunction "A1_A1") (pintype "passive+no_connect"))
    )
    (net (code "64") (name "unconnected-(D12-PadA2)") (class "Default")
      (node (ref "D12") (pin "A2") (pinfunction "A2_A2") (pintype "passive+no_connect"))
    )
    (net (code "65") (name "unconnected-(D12-PadA7)") (class "Default")
      (node (ref "D12") (pin "A7") (pinfunction "A7_A7") (pintype "passive+no_connect"))
    )
    (net (code "66") (name "unconnected-(D12-PadA8)") (class "Default")
      (node (ref "D12") (pin "A8") (pinfunction "A8_A8") (pintype "passive+no_connect"))
    )
    (net (code "67") (name "unconnected-(D12-PadA9)") (class "Default")
      (node (ref "D12") (pin "A9") (pinfunction "A9_A9") (pintype "passive+no_connect"))
    )
    (net (code "68") (name "unconnected-(D12-PadA10)") (class "Default")
      (node (ref "D12") (pin "A10") (pinfunction "A10_A10") (pintype "passive+no_connect"))
    )
    (net (code "69") (name "unconnected-(D12-PadA11)") (class "Default")
      (node (ref "D12") (pin "A11") (pinfunction "A11_A11") (pintype "passive+no_connect"))
    )
    (net (code "70") (name "unconnected-(D12-PadA12)") (class "Default")
      (node (ref "D12") (pin "A12") (pinfunction "A12_A12") (pintype "passive+no_connect"))
    )
    (net (code "71") (name "unconnected-(D12-PadA13)") (class "Default")
      (node (ref "D12") (pin "A13") (pinfunction "A13_A13") (pintype "passive+no_connect"))
    )
    (net (code "72") (name "unconnected-(D12-PadA14)") (class "Default")
      (node (ref "D12") (pin "A14") (pinfunction "A14_A14") (pintype "passive+no_connect"))
    )
    (net (code "73") (name "unconnected-(D12-PadB1)") (class "Default")
      (node (ref "D12") (pin "B1") (pinfunction "B1_B1") (pintype "passive+no_connect"))
    )
    (net (code "74") (name "unconnected-(D12-PadB7)") (class "Default")
      (node (ref "D12") (pin "B7") (pinfunction "B7_B7") (pintype "passive+no_connect"))
    )
    (net (code "75") (name "unconnected-(D12-PadB8)") (class "Default")
      (node (ref "D12") (pin "B8") (pinfunction "B8_B8") (pintype "passive+no_connect"))
    )
    (net (code "76") (name "unconnected-(D12-PadB9)") (class "Default")
      (node (ref "D12") (pin "B9") (pinfunction "B9_B9") (pintype "passive+no_connect"))
    )
    (net (code "77") (name "unconnected-(D12-PadB10)") (class "Default")
      (node (ref "D12") (pin "B10") (pinfunction "B10_B10") (pintype "passive+no_connect"))
    )
    (net (code "78") (name "unconnected-(D12-PadB11)") (class "Default")
      (node (ref "D12") (pin "B11") (pinfunction "B11_B11") (pintype "passive+no_connect"))
    )
    (net (code "79") (name "unconnected-(D12-PadB12)") (class "Default")
      (node (ref "D12") (pin "B12") (pinfunction "B12_B12") (pintype "passive+no_connect"))
    )
    (net (code "80") (name "unconnected-(D12-PadB13)") (class "Default")
      (node (ref "D12") (pin "B13") (pinfunction "B13_B13") (pintype "passive+no_connect"))
    )
    (net (code "81") (name "unconnected-(D12-PadB14)") (class "Default")
      (node (ref "D12") (pin "B14") (pinfunction "B14_B14") (pintype "passive+no_connect"))
    )
    (net (code "82") (name "unconnected-(D12-PadC1)") (class "Default")
      (node (ref "D12") (pin "C1") (pinfunction "C1_C1") (pintype "passive+no_connect"))
    )
    (net (code "83") (name "unconnected-(D12-PadC3)") (class "Default")
      (node (ref "D12") (pin "C3") (pinfunction "C3_C3") (pintype "passive+no_connect"))
    )
    (net (code "84") (name "unconnected-(D12-PadC5)") (class "Default")
      (node (ref "D12") (pin "C5") (pinfunction "C5_C5") (pintype "passive+no_connect"))
    )
    (net (code "85") (name "unconnected-(D12-PadC7)") (class "Default")
      (node (ref "D12") (pin "C7") (pinfunction "C7_C7") (pintype "passive+no_connect"))
    )
    (net (code "86") (name "unconnected-(D12-PadC8)") (class "Default")
      (node (ref "D12") (pin "C8") (pinfunction "C8_C8") (pintype "passive+no_connect"))
    )
    (net (code "87") (name "unconnected-(D12-PadC9)") (class "Default")
      (node (ref "D12") (pin "C9") (pinfunction "C9_C9") (pintype "passive+no_connect"))
    )
    (net (code "88") (name "unconnected-(D12-PadC10)") (class "Default")
      (node (ref "D12") (pin "C10") (pinfunction "C10_C10") (pintype "passive+no_connect"))
    )
    (net (code "89") (name "unconnected-(D12-PadC11)") (class "Default")
      (node (ref "D12") (pin "C11") (pinfunction "C11_C11") (pintype "passive+no_connect"))
    )
    (net (code "90") (name "unconnected-(D12-PadC12)") (class "Default")
      (node (ref "D12") (pin "C12") (pinfunction "C12_C12") (pintype "passive+no_connect"))
    )
    (net (code "91") (name "unconnected-(D12-PadC13)") (class "Default")
      (node (ref "D12") (pin "C13") (pinfunction "C13_C13") (pintype "passive+no_connect"))
    )
    (net (code "92") (name "unconnected-(D12-PadC14)") (class "Default")
      (node (ref "D12") (pin "C14") (pinfunction "C14_C14") (pintype "passive+no_connect"))
    )
    (net (code "93") (name "unconnected-(D12-PadD1)") (class "Default")
      (node (ref "D12") (pin "D1") (pinfunction "D1_D1") (pintype "passive+no_connect"))
    )
    (net (code "94") (name "unconnected-(D12-PadD2)") (class "Default")
      (node (ref "D12") (pin "D2") (pinfunction "D2_D2") (pintype "passive+no_connect"))
    )
    (net (code "95") (name "unconnected-(D12-PadD3)") (class "Default")
      (node (ref "D12") (pin "D3") (pinfunction "D3_D3") (pintype "passive+no_connect"))
    )
    (net (code "96") (name "unconnected-(D12-PadD4)") (class "Default")
      (node (ref "D12") (pin "D4") (pinfunction "D4_D4") (pintype "passive+no_connect"))
    )
    (net (code "97") (name "unconnected-(D12-PadD12)") (class "Default")
      (node (ref "D12") (pin "D12") (pinfunction "D12_D12") (pintype "passive+no_connect"))
    )
    (net (code "98") (name "unconnected-(D12-PadD13)") (class "Default")
      (node (ref "D12") (pin "D13") (pinfunction "D13_D13") (pintype "passive+no_connect"))
    )
    (net (code "99") (name "unconnected-(D12-PadD14)") (class "Default")
      (node (ref "D12") (pin "D14") (pinfunction "D14_D14") (pintype "passive+no_connect"))
    )
    (net (code "100") (name "unconnected-(D12-PadE1)") (class "Default")
      (node (ref "D12") (pin "E1") (pinfunction "E1_E1") (pintype "passive+no_connect"))
    )
    (net (code "101") (name "unconnected-(D12-PadE2)") (class "Default")
      (node (ref "D12") (pin "E2") (pinfunction "E2_E2") (pintype "passive+no_connect"))
    )
    (net (code "102") (name "unconnected-(D12-PadE3)") (class "Default")
      (node (ref "D12") (pin "E3") (pinfunction "E3_E3") (pintype "passive+no_connect"))
    )
    (net (code "103") (name "unconnected-(D12-PadE5)") (class "Default")
      (node (ref "D12") (pin "E5") (pinfunction "E5_E5") (pintype "passive+no_connect"))
    )
    (net (code "104") (name "unconnected-(D12-PadE8)") (class "Default")
      (node (ref "D12") (pin "E8") (pinfunction "E8_E8") (pintype "passive+no_connect"))
    )
    (net (code "105") (name "unconnected-(D12-PadE9)") (class "Default")
      (node (ref "D12") (pin "E9") (pinfunction "E9_E9") (pintype "passive+no_connect"))
    )
    (net (code "106") (name "unconnected-(D12-PadE10)") (class "Default")
      (node (ref "D12") (pin "E10") (pinfunction "E10_E10") (pintype "passive+no_connect"))
    )
    (net (code "107") (name "unconnected-(D12-PadE12)") (class "Default")
      (node (ref "D12") (pin "E12") (pinfunction "E12_E12") (pintype "passive+no_connect"))
    )
    (net (code "108") (name "unconnected-(D12-PadE13)") (class "Default")
      (node (ref "D12") (pin "E13") (pinfunction "E13_E13") (pintype "passive+no_connect"))
    )
    (net (code "109") (name "unconnected-(D12-PadE14)") (class "Default")
      (node (ref "D12") (pin "E14") (pinfunction "E14_E14") (pintype "passive+no_connect"))
    )
    (net (code "110") (name "unconnected-(D12-PadF1)") (class "Default")
      (node (ref "D12") (pin "F1") (pinfunction "F1_F1") (pintype "passive+no_connect"))
    )
    (net (code "111") (name "unconnected-(D12-PadF2)") (class "Default")
      (node (ref "D12") (pin "F2") (pinfunction "F2_F2") (pintype "passive+no_connect"))
    )
    (net (code "112") (name "unconnected-(D12-PadF3)") (class "Default")
      (node (ref "D12") (pin "F3") (pinfunction "F3_F3") (pintype "passive+no_connect"))
    )
    (net (code "113") (name "unconnected-(D12-PadF10)") (class "Default")
      (node (ref "D12") (pin "F10") (pinfunction "F10_F10") (pintype "passive+no_connect"))
    )
    (net (code "114") (name "unconnected-(D12-PadF12)") (class "Default")
      (node (ref "D12") (pin "F12") (pinfunction "F12_F12") (pintype "passive+no_connect"))
    )
    (net (code "115") (name "unconnected-(D12-PadF13)") (class "Default")
      (node (ref "D12") (pin "F13") (pinfunction "F13_F13") (pintype "passive+no_connect"))
    )
    (net (code "116") (name "unconnected-(D12-PadF14)") (class "Default")
      (node (ref "D12") (pin "F14") (pinfunction "F14_F14") (pintype "passive+no_connect"))
    )
    (net (code "117") (name "unconnected-(D12-PadG1)") (class "Default")
      (node (ref "D12") (pin "G1") (pinfunction "G1_G1") (pintype "passive+no_connect"))
    )
    (net (code "118") (name "unconnected-(D12-PadG2)") (class "Default")
      (node (ref "D12") (pin "G2") (pinfunction "G2_G2") (pintype "passive+no_connect"))
    )
    (net (code "119") (name "unconnected-(D12-PadG3)") (class "Default")
      (node (ref "D12") (pin "G3") (pinfunction "G3_G3") (pintype "passive+no_connect"))
    )
    (net (code "120") (name "unconnected-(D12-PadG10)") (class "Default")
      (node (ref "D12") (pin "G10") (pinfunction "G10_G10") (pintype "passive+no_connect"))
    )
    (net (code "121") (name "unconnected-(D12-PadG12)") (class "Default")
      (node (ref "D12") (pin "G12") (pinfunction "G12_G12") (pintype "passive+no_connect"))
    )
    (net (code "122") (name "unconnected-(D12-PadG13)") (class "Default")
      (node (ref "D12") (pin "G13") (pinfunction "G13_G13") (pintype "passive+no_connect"))
    )
    (net (code "123") (name "unconnected-(D12-PadG14)") (class "Default")
      (node (ref "D12") (pin "G14") (pinfunction "G14_G14") (pintype "passive+no_connect"))
    )
    (net (code "124") (name "unconnected-(D12-PadH1)") (class "Default")
      (node (ref "D12") (pin "H1") (pinfunction "H1_H1") (pintype "passive+no_connect"))
    )
    (net (code "125") (name "unconnected-(D12-PadH2)") (class "Default")
      (node (ref "D12") (pin "H2") (pinfunction "H2_H2") (pintype "passive+no_connect"))
    )
    (net (code "126") (name "unconnected-(D12-PadH3)") (class "Default")
      (node (ref "D12") (pin "H3") (pinfunction "H3_H3") (pintype "passive+no_connect"))
    )
    (net (code "127") (name "unconnected-(D12-PadH12)") (class "Default")
      (node (ref "D12") (pin "H12") (pinfunction "H12_H12") (pintype "passive+no_connect"))
    )
    (net (code "128") (name "unconnected-(D12-PadH13)") (class "Default")
      (node (ref "D12") (pin "H13") (pinfunction "H13_H13") (pintype "passive+no_connect"))
    )
    (net (code "129") (name "unconnected-(D12-PadH14)") (class "Default")
      (node (ref "D12") (pin "H14") (pinfunction "H14_H14") (pintype "passive+no_connect"))
    )
    (net (code "130") (name "unconnected-(D12-PadJ1)") (class "Default")
      (node (ref "D12") (pin "J1") (pinfunction "J1_J1") (pintype "passive+no_connect"))
    )
    (net (code "131") (name "unconnected-(D12-PadJ2)") (class "Default")
      (node (ref "D12") (pin "J2") (pinfunction "J2_J2") (pintype "passive+no_connect"))
    )
    (net (code "132") (name "unconnected-(D12-PadJ3)") (class "Default")
      (node (ref "D12") (pin "J3") (pinfunction "J3_J3") (pintype "passive+no_connect"))
    )
    (net (code "133") (name "unconnected-(D12-PadJ12)") (class "Default")
      (node (ref "D12") (pin "J12") (pinfunction "J12_J12") (pintype "passive+no_connect"))
    )
    (net (code "134") (name "unconnected-(D12-PadJ13)") (class "Default")
      (node (ref "D12") (pin "J13") (pinfunction "J13_J13") (pintype "passive+no_connect"))
    )
    (net (code "135") (name "unconnected-(D12-PadJ14)") (class "Default")
      (node (ref "D12") (pin "J14") (pinfunction "J14_J14") (pintype "passive+no_connect"))
    )
    (net (code "136") (name "unconnected-(D12-PadK1)") (class "Default")
      (node (ref "D12") (pin "K1") (pinfunction "K1_K1") (pintype "passive+no_connect"))
    )
    (net (code "137") (name "unconnected-(D12-PadK2)") (class "Default")
      (node (ref "D12") (pin "K2") (pinfunction "K2_K2") (pintype "passive+no_connect"))
    )
    (net (code "138") (name "unconnected-(D12-PadK3)") (class "Default")
      (node (ref "D12") (pin "K3") (pinfunction "K3_K3") (pintype "passive+no_connect"))
    )
    (net (code "139") (name "unconnected-(D12-PadK6)") (class "Default")
      (node (ref "D12") (pin "K6") (pinfunction "K6_K6") (pintype "passive+no_connect"))
    )
    (net (code "140") (name "unconnected-(D12-PadK7)") (class "Default")
      (node (ref "D12") (pin "K7") (pinfunction "K7_K7") (pintype "passive+no_connect"))
    )
    (net (code "141") (name "unconnected-(D12-PadK10)") (class "Default")
      (node (ref "D12") (pin "K10") (pinfunction "K10_K10") (pintype "passive+no_connect"))
    )
    (net (code "142") (name "unconnected-(D12-PadK12)") (class "Default")
      (node (ref "D12") (pin "K12") (pinfunction "K12_K12") (pintype "passive+no_connect"))
    )
    (net (code "143") (name "unconnected-(D12-PadK13)") (class "Default")
      (node (ref "D12") (pin "K13") (pinfunction "K13_K13") (pintype "passive+no_connect"))
    )
    (net (code "144") (name "unconnected-(D12-PadK14)") (class "Default")
      (node (ref "D12") (pin "K14") (pinfunction "K14_K14") (pintype "passive+no_connect"))
    )
    (net (code "145") (name "unconnected-(D12-PadL1)") (class "Default")
      (node (ref "D12") (pin "L1") (pinfunction "L1_L1") (pintype "passive+no_connect"))
    )
    (net (code "146") (name "unconnected-(D12-PadL2)") (class "Default")
      (node (ref "D12") (pin "L2") (pinfunction "L2_L2") (pintype "passive+no_connect"))
    )
    (net (code "147") (name "unconnected-(D12-PadL3)") (class "Default")
      (node (ref "D12") (pin "L3") (pinfunction "L3_L3") (pintype "passive+no_connect"))
    )
    (net (code "148") (name "unconnected-(D12-PadL12)") (class "Default")
      (node (ref "D12") (pin "L12") (pinfunction "L12_L12") (pintype "passive+no_connect"))
    )
    (net (code "149") (name "unconnected-(D12-PadL13)") (class "Default")
      (node (ref "D12") (pin "L13") (pinfunction "L13_L13") (pintype "passive+no_connect"))
    )
    (net (code "150") (name "unconnected-(D12-PadL14)") (class "Default")
      (node (ref "D12") (pin "L14") (pinfunction "L14_L14") (pintype "passive+no_connect"))
    )
    (net (code "151") (name "unconnected-(D12-PadM1)") (class "Default")
      (node (ref "D12") (pin "M1") (pinfunction "M1_M1") (pintype "passive+no_connect"))
    )
    (net (code "152") (name "unconnected-(D12-PadM2)") (class "Default")
      (node (ref "D12") (pin "M2") (pinfunction "M2_M2") (pintype "passive+no_connect"))
    )
    (net (code "153") (name "unconnected-(D12-PadM3)") (class "Default")
      (node (ref "D12") (pin "M3") (pinfunction "M3_M3") (pintype "passive+no_connect"))
    )
    (net (code "154") (name "unconnected-(D12-PadM7)") (class "Default")
      (node (ref "D12") (pin "M7") (pinfunction "M7_M7") (pintype "passive+no_connect"))
    )
    (net (code "155") (name "unconnected-(D12-PadM8)") (class "Default")
      (node (ref "D12") (pin "M8") (pinfunction "M8_M8") (pintype "passive+no_connect"))
    )
    (net (code "156") (name "unconnected-(D12-PadM9)") (class "Default")
      (node (ref "D12") (pin "M9") (pinfunction "M9_M9") (pintype "passive+no_connect"))
    )
    (net (code "157") (name "unconnected-(D12-PadM10)") (class "Default")
      (node (ref "D12") (pin "M10") (pinfunction "M10_M10") (pintype "passive+no_connect"))
    )
    (net (code "158") (name "unconnected-(D12-PadM11)") (class "Default")
      (node (ref "D12") (pin "M11") (pinfunction "M11_M11") (pintype "passive+no_connect"))
    )
    (net (code "159") (name "unconnected-(D12-PadM12)") (class "Default")
      (node (ref "D12") (pin "M12") (pinfunction "M12_M12") (pintype "passive+no_connect"))
    )
    (net (code "160") (name "unconnected-(D12-PadM13)") (class "Default")
      (node (ref "D12") (pin "M13") (pinfunction "M13_M13") (pintype "passive+no_connect"))
    )
    (net (code "161") (name "unconnected-(D12-PadM14)") (class "Default")
      (node (ref "D12") (pin "M14") (pinfunction "M14_M14") (pintype "passive+no_connect"))
    )
    (net (code "162") (name "unconnected-(D12-PadN1)") (class "Default")
      (node (ref "D12") (pin "N1") (pinfunction "N1_N1") (pintype "passive+no_connect"))
    )
    (net (code "163") (name "unconnected-(D12-PadN3)") (class "Default")
      (node (ref "D12") (pin "N3") (pinfunction "N3_N3") (pintype "passive+no_connect"))
    )
    (net (code "164") (name "unconnected-(D12-PadN6)") (class "Default")
      (node (ref "D12") (pin "N6") (pinfunction "N6_N6") (pintype "passive+no_connect"))
    )
    (net (code "165") (name "unconnected-(D12-PadN7)") (class "Default")
      (node (ref "D12") (pin "N7") (pinfunction "N7_N7") (pintype "passive+no_connect"))
    )
    (net (code "166") (name "unconnected-(D12-PadN8)") (class "Default")
      (node (ref "D12") (pin "N8") (pinfunction "N8_N8") (pintype "passive+no_connect"))
    )
    (net (code "167") (name "unconnected-(D12-PadN9)") (class "Default")
      (node (ref "D12") (pin "N9") (pinfunction "N9_N9") (pintype "passive+no_connect"))
    )
    (net (code "168") (name "unconnected-(D12-PadN10)") (class "Default")
      (node (ref "D12") (pin "N10") (pinfunction "N10_N10") (pintype "passive+no_connect"))
    )
    (net (code "169") (name "unconnected-(D12-PadN11)") (class "Default")
      (node (ref "D12") (pin "N11") (pinfunction "N11_N11") (pintype "passive+no_connect"))
    )
    (net (code "170") (name "unconnected-(D12-PadN12)") (class "Default")
      (node (ref "D12") (pin "N12") (pinfunction "N12_N12") (pintype "passive+no_connect"))
    )
    (net (code "171") (name "unconnected-(D12-PadN13)") (class "Default")
      (node (ref "D12") (pin "N13") (pinfunction "N13_N13") (pintype "passive+no_connect"))
    )
    (net (code "172") (name "unconnected-(D12-PadN14)") (class "Default")
      (node (ref "D12") (pin "N14") (pinfunction "N14_N14") (pintype "passive+no_connect"))
    )
    (net (code "173") (name "unconnected-(D12-PadP1)") (class "Default")
      (node (ref "D12") (pin "P1") (pinfunction "P1_P1") (pintype "passive+no_connect"))
    )
    (net (code "174") (name "unconnected-(D12-PadP2)") (class "Default")
      (node (ref "D12") (pin "P2") (pinfunction "P2_P2") (pintype "passive+no_connect"))
    )
    (net (code "175") (name "unconnected-(D12-PadP7)") (class "Default")
      (node (ref "D12") (pin "P7") (pinfunction "P7_P7") (pintype "passive+no_connect"))
    )
    (net (code "176") (name "unconnected-(D12-PadP8)") (class "Default")
      (node (ref "D12") (pin "P8") (pinfunction "P8_P8") (pintype "passive+no_connect"))
    )
    (net (code "177") (name "unconnected-(D12-PadP9)") (class "Default")
      (node (ref "D12") (pin "P9") (pinfunction "P9_P9") (pintype "passive+no_connect"))
    )
    (net (code "178") (name "unconnected-(D12-PadP10)") (class "Default")
      (node (ref "D12") (pin "P10") (pinfunction "P10_P10") (pintype "passive+no_connect"))
    )
    (net (code "179") (name "unconnected-(D12-PadP11)") (class "Default")
      (node (ref "D12") (pin "P11") (pinfunction "P11_P11") (pintype "passive+no_connect"))
    )
    (net (code "180") (name "unconnected-(D12-PadP12)") (class "Default")
      (node (ref "D12") (pin "P12") (pinfunction "P12_P12") (pintype "passive+no_connect"))
    )
    (net (code "181") (name "unconnected-(D12-PadP13)") (class "Default")
      (node (ref "D12") (pin "P13") (pinfunction "P13_P13") (pintype "passive+no_connect"))
    )
    (net (code "182") (name "unconnected-(D12-PadP14)") (class "Default")
      (node (ref "D12") (pin "P14") (pinfunction "P14_P14") (pintype "passive+no_connect"))
    )
  )
)
